# AB_Amplifier.net
KiCad netlist of a schematic drawn in Altium Designer
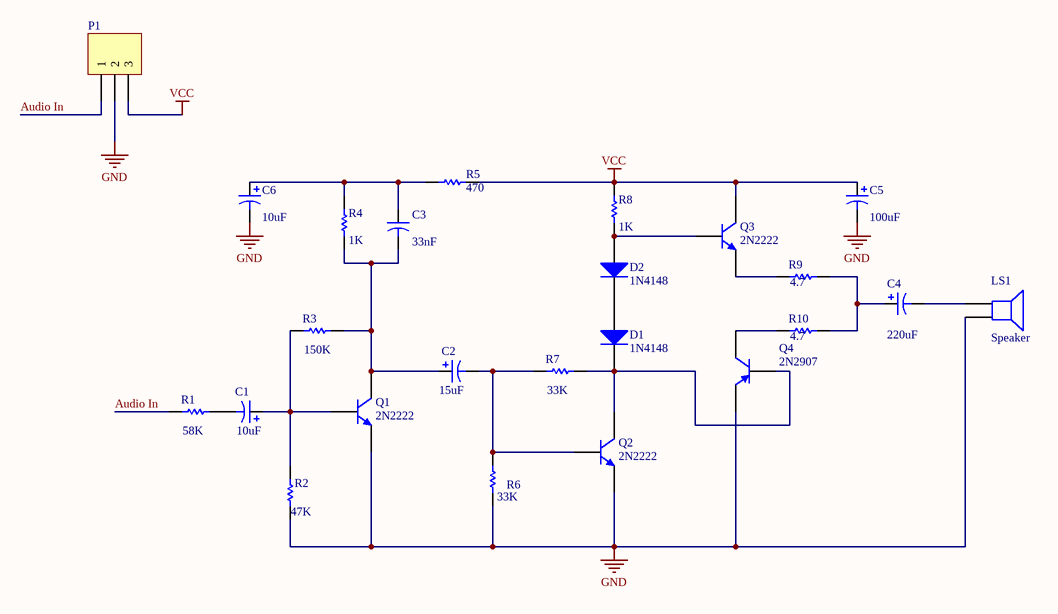
[diagram p0: AB_Amplifier.SchDoc]

(export (version "E")
  (design (tool "Eeschema 10.0.6"))
  (components
    (comp (ref "C1")
      (value "10uF")
      (footprint "CAPR5-4X5")
      (description "Polarized Capacitor (Radial)")
      (fields (field (name "Comment") "Cap Pol1") (field (name "PUBLISHER") "Altium Limited"))
      (libsource (lib "Miscellaneous Devices") (part "Cap Pol1"))
    )
    (comp (ref "C2")
      (value "15uF")
      (footprint "CAPR5-4X5")
      (description "Polarized Capacitor (Radial)")
      (fields (field (name "Comment") "Cap Pol1") (field (name "PUBLISHER") "Altium Limited"))
      (libsource (lib "Miscellaneous Devices") (part "Cap Pol1"))
    )
    (comp (ref "C3")
      (value "33nF")
      (footprint "CAPR5-4X5")
      (description "Capacitor")
      (fields (field (name "Comment") "Cap2") (field (name "PUBLISHER") "Altium Limited"))
      (libsource (lib "Miscellaneous Devices") (part "Cap2"))
    )
    (comp (ref "C4")
      (value "220uF")
      (footprint "CAPR5-4X5")
      (description "Polarized Capacitor (Radial)")
      (fields (field (name "Comment") "Cap Pol1") (field (name "PUBLISHER") "Altium Limited"))
      (libsource (lib "Miscellaneous Devices") (part "Cap Pol1"))
    )
    (comp (ref "C5")
      (value "100uF")
      (footprint "CAPR5-4X5")
      (description "Polarized Capacitor (Radial)")
      (fields (field (name "Comment") "Cap Pol1") (field (name "PUBLISHER") "Altium Limited"))
      (libsource (lib "Miscellaneous Devices") (part "Cap Pol1"))
    )
    (comp (ref "C6")
      (value "10uF")
      (footprint "CAPR5-4X5")
      (description "Polarized Capacitor (Radial)")
      (fields (field (name "Comment") "Cap Pol1") (field (name "PUBLISHER") "Altium Limited"))
      (libsource (lib "Miscellaneous Devices") (part "Cap Pol1"))
    )
    (comp (ref "D1")
      (value "1N4148")
      (footprint "DO-35")
      (description "High Conductance Fast Diode")
      (fields (field (name "PUBLISHER") "Altium Limited"))
      (libsource (lib "Miscellaneous Devices") (part "Diode 1N4148"))
    )
    (comp (ref "D2")
      (value "1N4148")
      (footprint "DO-35")
      (description "High Conductance Fast Diode")
      (fields (field (name "PUBLISHER") "Altium Limited"))
      (libsource (lib "Miscellaneous Devices") (part "Diode 1N4148"))
    )
    (comp (ref "LS1")
      (value "Speaker")
      (footprint "PIN2")
      (description "Loudspeaker")
      (fields (field (name "PUBLISHER") "Altium Limited"))
      (libsource (lib "Miscellaneous Devices") (part "Speaker"))
    )
    (comp (ref "P1")
      (value "Header 3")
      (footprint "HDR1X3")
      (description "Header, 3-Pin")
      (fields (field (name "PUBLISHER") "Altium Limited"))
      (libsource (lib "Miscellaneous Connectors") (part "Header 3"))
    )
    (comp (ref "Q1")
      (value "2N2222")
      (footprint "TO-226-AA")
      (description "NPN Bipolar Transistor")
      (fields (field (name "PUBLISHER") "Altium Limited"))
      (libsource (lib "Miscellaneous Devices") (part "NPN"))
    )
    (comp (ref "Q2")
      (value "2N2222")
      (footprint "TO-226-AA")
      (description "NPN Bipolar Transistor")
      (fields (field (name "PUBLISHER") "Altium Limited"))
      (libsource (lib "Miscellaneous Devices") (part "NPN"))
    )
    (comp (ref "Q3")
      (value "2N2222")
      (footprint "TO-226-AA")
      (description "NPN Bipolar Transistor")
      (fields (field (name "PUBLISHER") "Altium Limited"))
      (libsource (lib "Miscellaneous Devices") (part "NPN"))
    )
    (comp (ref "Q4")
      (value "2N2907")
      (footprint "TO-226-AA")
      (description "PNP Bipolar Transistor")
      (fields (field (name "PUBLISHER") "Altium Limited"))
      (libsource (lib "Miscellaneous Devices") (part "PNP"))
    )
    (comp (ref "R1")
      (value "58K")
      (footprint "AXIAL-0.3")
      (description "Resistor")
      (fields (field (name "Comment") "Res1") (field (name "PUBLISHER") "Altium Limited"))
      (libsource (lib "Miscellaneous Devices") (part "Res1"))
    )
    (comp (ref "R2")
      (value "47K")
      (footprint "AXIAL-0.3")
      (description "Resistor")
      (fields (field (name "Comment") "Res1") (field (name "PUBLISHER") "Altium Limited"))
      (libsource (lib "Miscellaneous Devices") (part "Res1"))
    )
    (comp (ref "R3")
      (value "150K")
      (footprint "AXIAL-0.3")
      (description "Resistor")
      (fields (field (name "Comment") "Res1") (field (name "PUBLISHER") "Altium Limited"))
      (libsource (lib "Miscellaneous Devices") (part "Res1"))
    )
    (comp (ref "R4")
      (value "1K")
      (footprint "AXIAL-0.3")
      (description "Resistor")
      (fields (field (name "Comment") "Res1") (field (name "PUBLISHER") "Altium Limited"))
      (libsource (lib "Miscellaneous Devices") (part "Res1"))
    )
    (comp (ref "R5")
      (value "470")
      (footprint "AXIAL-0.3")
      (description "Resistor")
      (fields (field (name "Comment") "Res1") (field (name "PUBLISHER") "Altium Limited"))
      (libsource (lib "Miscellaneous Devices") (part "Res1"))
    )
    (comp (ref "R6")
      (value "33K")
      (footprint "AXIAL-0.3")
      (description "Resistor")
      (fields (field (name "Comment") "Res1") (field (name "PUBLISHER") "Altium Limited"))
      (libsource (lib "Miscellaneous Devices") (part "Res1"))
    )
    (comp (ref "R7")
      (value "33K")
      (footprint "AXIAL-0.3")
      (description "Resistor")
      (fields (field (name "Comment") "Res1") (field (name "PUBLISHER") "Altium Limited"))
      (libsource (lib "Miscellaneous Devices") (part "Res1"))
    )
    (comp (ref "R8")
      (value "1K")
      (footprint "AXIAL-0.3")
      (description "Resistor")
      (fields (field (name "Comment") "Res1") (field (name "PUBLISHER") "Altium Limited"))
      (libsource (lib "Miscellaneous Devices") (part "Res1"))
    )
    (comp (ref "R9")
      (value "4.7")
      (footprint "AXIAL-0.3")
      (description "Resistor")
      (fields (field (name "Comment") "Res1") (field (name "PUBLISHER") "Altium Limited"))
      (libsource (lib "Miscellaneous Devices") (part "Res1"))
    )
    (comp (ref "R10")
      (value "4.7")
      (footprint "AXIAL-0.3")
      (description "Resistor")
      (fields (field (name "PUBLISHER") "Altium Limited"))
      (libsource (lib "Miscellaneous Devices") (part "Res1"))
    )
  )
  (nets
    (net (code "1") (name "/Audio In") (class "Default")
      (node (ref "P1") (pin "1") (pinfunction "1_1") (pintype "passive"))
      (node (ref "R1") (pin "1") (pinfunction "1_1") (pintype "passive"))
    )
    (net (code "2") (name "GND") (class "Default")
      (node (ref "C5") (pin "2") (pinfunction "2_2") (pintype "passive"))
      (node (ref "C6") (pin "2") (pinfunction "2_2") (pintype "passive"))
      (node (ref "LS1") (pin "2") (pinfunction "2_2") (pintype "passive"))
      (node (ref "P1") (pin "2") (pinfunction "2_2") (pintype "passive"))
      (node (ref "Q1") (pin "3") (pinfunction "E_3") (pintype "passive"))
      (node (ref "Q2") (pin "3") (pinfunction "E_3") (pintype "passive"))
      (node (ref "Q4") (pin "3") (pinfunction "E_3") (pintype "passive"))
      (node (ref "R2") (pin "1") (pinfunction "1_1") (pintype "passive"))
      (node (ref "R6") (pin "2") (pinfunction "2_2") (pintype "passive"))
    )
    (net (code "3") (name "Net-(C1-Pad2)") (class "Default")
      (node (ref "C1") (pin "2") (pinfunction "2_2") (pintype "passive"))
      (node (ref "R1") (pin "2") (pinfunction "2_2") (pintype "passive"))
    )
    (net (code "4") (name "Net-(C3-Pad1)") (class "Default")
      (node (ref "C3") (pin "1") (pinfunction "1_1") (pintype "passive"))
      (node (ref "C6") (pin "1") (pinfunction "1_1") (pintype "passive"))
      (node (ref "R4") (pin "1") (pinfunction "1_1") (pintype "passive"))
      (node (ref "R5") (pin "1") (pinfunction "1_1") (pintype "passive"))
    )
    (net (code "5") (name "Net-(C4-Pad1)") (class "Default")
      (node (ref "C4") (pin "1") (pinfunction "1_1") (pintype "passive"))
      (node (ref "R10") (pin "2") (pinfunction "2_2") (pintype "passive"))
      (node (ref "R9") (pin "2") (pinfunction "2_2") (pintype "passive"))
    )
    (net (code "6") (name "Net-(C4-Pad2)") (class "Default")
      (node (ref "C4") (pin "2") (pinfunction "2_2") (pintype "passive"))
      (node (ref "LS1") (pin "1") (pinfunction "1_1") (pintype "passive"))
    )
    (net (code "7") (name "Net-(D1-A)") (class "Default")
      (node (ref "D1") (pin "1") (pinfunction "A_1") (pintype "passive"))
      (node (ref "D2") (pin "2") (pinfunction "K_2") (pintype "passive"))
    )
    (net (code "8") (name "Net-(D1-K)") (class "Default")
      (node (ref "D1") (pin "2") (pinfunction "K_2") (pintype "passive"))
      (node (ref "Q2") (pin "1") (pinfunction "C_1") (pintype "passive"))
      (node (ref "Q4") (pin "2") (pinfunction "B_2") (pintype "passive"))
      (node (ref "R7") (pin "1") (pinfunction "1_1") (pintype "passive"))
    )
    (net (code "9") (name "Net-(D2-A)") (class "Default")
      (node (ref "D2") (pin "1") (pinfunction "A_1") (pintype "passive"))
      (node (ref "Q3") (pin "2") (pinfunction "B_2") (pintype "passive"))
      (node (ref "R8") (pin "1") (pinfunction "1_1") (pintype "passive"))
    )
    (net (code "10") (name "Net-(Q1-B)") (class "Default")
      (node (ref "C1") (pin "1") (pinfunction "1_1") (pintype "passive"))
      (node (ref "Q1") (pin "2") (pinfunction "B_2") (pintype "passive"))
      (node (ref "R2") (pin "2") (pinfunction "2_2") (pintype "passive"))
      (node (ref "R3") (pin "2") (pinfunction "2_2") (pintype "passive"))
    )
    (net (code "11") (name "Net-(Q1-C)") (class "Default")
      (node (ref "C2") (pin "1") (pinfunction "1_1") (pintype "passive"))
      (node (ref "C3") (pin "2") (pinfunction "2_2") (pintype "passive"))
      (node (ref "Q1") (pin "1") (pinfunction "C_1") (pintype "passive"))
      (node (ref "R3") (pin "1") (pinfunction "1_1") (pintype "passive"))
      (node (ref "R4") (pin "2") (pinfunction "2_2") (pintype "passive"))
    )
    (net (code "12") (name "Net-(Q2-B)") (class "Default")
      (node (ref "C2") (pin "2") (pinfunction "2_2") (pintype "passive"))
      (node (ref "Q2") (pin "2") (pinfunction "B_2") (pintype "passive"))
      (node (ref "R6") (pin "1") (pinfunction "1_1") (pintype "passive"))
      (node (ref "R7") (pin "2") (pinfunction "2_2") (pintype "passive"))
    )
    (net (code "13") (name "Net-(Q3-E)") (class "Default")
      (node (ref "Q3") (pin "3") (pinfunction "E_3") (pintype "passive"))
      (node (ref "R9") (pin "1") (pinfunction "1_1") (pintype "passive"))
    )
    (net (code "14") (name "Net-(Q4-C)") (class "Default")
      (node (ref "Q4") (pin "1") (pinfunction "C_1") (pintype "passive"))
      (node (ref "R10") (pin "1") (pinfunction "1_1") (pintype "passive"))
    )
    (net (code "15") (name "VCC") (class "Default")
      (node (ref "C5") (pin "1") (pinfunction "1_1") (pintype "passive"))
      (node (ref "P1") (pin "3") (pinfunction "3_3") (pintype "passive"))
      (node (ref "Q3") (pin "1") (pinfunction "C_1") (pintype "passive"))
      (node (ref "R5") (pin "2") (pinfunction "2_2") (pintype "passive"))
      (node (ref "R8") (pin "2") (pinfunction "2_2") (pintype "passive"))
    )
  )
)
